# untitled.net
KiCad netlist of a schematic drawn in EAGLE
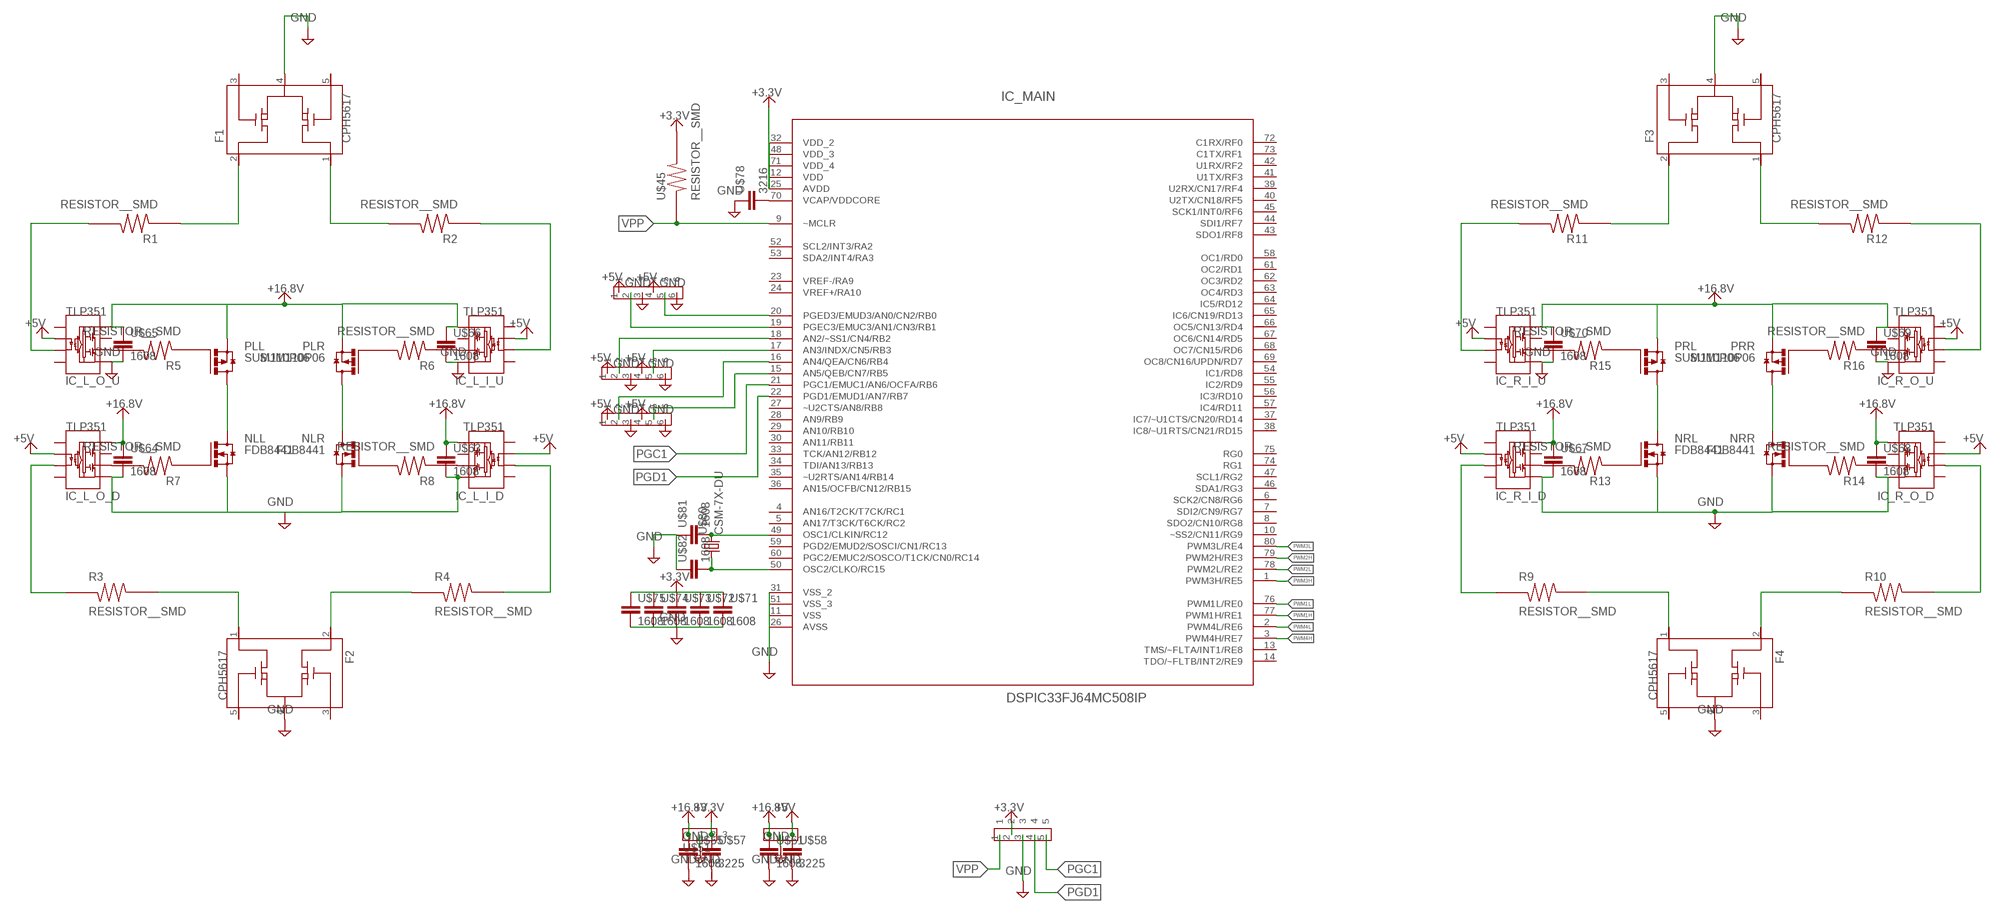
[diagram p0: schematic, sheet 1]

(export (version "E")
  (design (tool "Eeschema 10.0.6"))
  (components
    (comp (ref "F1")
      (value "CPH5617")
      (footprint "eagle-import:CHP-5")
      (libsource (lib "eagle-import") (part "CPH5617"))
    )
    (comp (ref "F2")
      (value "CPH5617")
      (footprint "eagle-import:CHP-5")
      (libsource (lib "eagle-import") (part "CPH5617"))
    )
    (comp (ref "F3")
      (value "CPH5617")
      (footprint "eagle-import:CHP-5")
      (libsource (lib "eagle-import") (part "CPH5617"))
    )
    (comp (ref "F4")
      (value "CPH5617")
      (footprint "eagle-import:CHP-5")
      (libsource (lib "eagle-import") (part "CPH5617"))
    )
    (comp (ref "IC_L_I_D")
      (value "TLP351")
      (footprint "eagle-import:DIL08")
      (libsource (lib "eagle-import") (part "TLP351"))
    )
    (comp (ref "IC_L_I_U")
      (value "TLP351")
      (footprint "eagle-import:DIL08")
      (libsource (lib "eagle-import") (part "TLP351"))
    )
    (comp (ref "IC_L_O_D")
      (value "TLP351")
      (footprint "eagle-import:DIL08")
      (libsource (lib "eagle-import") (part "TLP351"))
    )
    (comp (ref "IC_L_O_U")
      (value "TLP351")
      (footprint "eagle-import:DIL08")
      (libsource (lib "eagle-import") (part "TLP351"))
    )
    (comp (ref "IC_MAIN")
      (value "DSPIC33FJ64MC508IP")
      (footprint "eagle-import:QFP50P1400X1400X120-80N")
      (libsource (lib "eagle-import") (part "DSPIC33FJ64MC508IP"))
    )
    (comp (ref "IC_R_I_D")
      (value "TLP351")
      (footprint "eagle-import:DIL08")
      (libsource (lib "eagle-import") (part "TLP351"))
    )
    (comp (ref "IC_R_I_U")
      (value "TLP351")
      (footprint "eagle-import:DIL08")
      (libsource (lib "eagle-import") (part "TLP351"))
    )
    (comp (ref "IC_R_O_D")
      (value "TLP351")
      (footprint "eagle-import:DIL08")
      (libsource (lib "eagle-import") (part "TLP351"))
    )
    (comp (ref "IC_R_O_U")
      (value "TLP351")
      (footprint "eagle-import:DIL08")
      (libsource (lib "eagle-import") (part "TLP351"))
    )
    (comp (ref "NLL")
      (value "FDB8441")
      (footprint "eagle-import:TO-263")
      (libsource (lib "eagle-import") (part "FDB8441"))
    )
    (comp (ref "NLR")
      (value "FDB8441")
      (footprint "eagle-import:TO-263")
      (libsource (lib "eagle-import") (part "FDB8441"))
    )
    (comp (ref "NRL")
      (value "FDB8441")
      (footprint "eagle-import:TO-263")
      (libsource (lib "eagle-import") (part "FDB8441"))
    )
    (comp (ref "NRR")
      (value "FDB8441")
      (footprint "eagle-import:TO-263")
      (libsource (lib "eagle-import") (part "FDB8441"))
    )
    (comp (ref "PLL")
      (value "SUM110P06")
      (footprint "eagle-import:TO-263")
      (libsource (lib "eagle-import") (part "SUM110P06"))
    )
    (comp (ref "PLR")
      (value "SUM110P06")
      (footprint "eagle-import:TO-263")
      (libsource (lib "eagle-import") (part "SUM110P06"))
    )
    (comp (ref "PRL")
      (value "SUM110P06")
      (footprint "eagle-import:TO-263")
      (libsource (lib "eagle-import") (part "SUM110P06"))
    )
    (comp (ref "PRR")
      (value "SUM110P06")
      (footprint "eagle-import:TO-263")
      (libsource (lib "eagle-import") (part "SUM110P06"))
    )
    (comp (ref "R1")
      (value "RESISTOR__SMD")
      (footprint "eagle-import:1608")
      (libsource (lib "eagle-import") (part "RESISTOR__SMD"))
    )
    (comp (ref "R2")
      (value "RESISTOR__SMD")
      (footprint "eagle-import:1608")
      (libsource (lib "eagle-import") (part "RESISTOR__SMD"))
    )
    (comp (ref "R3")
      (value "RESISTOR__SMD")
      (footprint "eagle-import:1608")
      (libsource (lib "eagle-import") (part "RESISTOR__SMD"))
    )
    (comp (ref "R4")
      (value "RESISTOR__SMD")
      (footprint "eagle-import:1608")
      (libsource (lib "eagle-import") (part "RESISTOR__SMD"))
    )
    (comp (ref "R5")
      (value "RESISTOR__SMD")
      (footprint "eagle-import:1608")
      (libsource (lib "eagle-import") (part "RESISTOR__SMD"))
    )
    (comp (ref "R6")
      (value "RESISTOR__SMD")
      (footprint "eagle-import:1608")
      (libsource (lib "eagle-import") (part "RESISTOR__SMD"))
    )
    (comp (ref "R7")
      (value "RESISTOR__SMD")
      (footprint "eagle-import:1608")
      (libsource (lib "eagle-import") (part "RESISTOR__SMD"))
    )
    (comp (ref "R8")
      (value "RESISTOR__SMD")
      (footprint "eagle-import:1608")
      (libsource (lib "eagle-import") (part "RESISTOR__SMD"))
    )
    (comp (ref "R9")
      (value "RESISTOR__SMD")
      (footprint "eagle-import:1608")
      (libsource (lib "eagle-import") (part "RESISTOR__SMD"))
    )
    (comp (ref "R10")
      (value "RESISTOR__SMD")
      (footprint "eagle-import:1608")
      (libsource (lib "eagle-import") (part "RESISTOR__SMD"))
    )
    (comp (ref "R11")
      (value "RESISTOR__SMD")
      (footprint "eagle-import:1608")
      (libsource (lib "eagle-import") (part "RESISTOR__SMD"))
    )
    (comp (ref "R12")
      (value "RESISTOR__SMD")
      (footprint "eagle-import:1608")
      (libsource (lib "eagle-import") (part "RESISTOR__SMD"))
    )
    (comp (ref "R13")
      (value "RESISTOR__SMD")
      (footprint "eagle-import:1608")
      (libsource (lib "eagle-import") (part "RESISTOR__SMD"))
    )
    (comp (ref "R14")
      (value "RESISTOR__SMD")
      (footprint "eagle-import:1608")
      (libsource (lib "eagle-import") (part "RESISTOR__SMD"))
    )
    (comp (ref "R15")
      (value "RESISTOR__SMD")
      (footprint "eagle-import:1608")
      (libsource (lib "eagle-import") (part "RESISTOR__SMD"))
    )
    (comp (ref "R16")
      (value "RESISTOR__SMD")
      (footprint "eagle-import:1608")
      (libsource (lib "eagle-import") (part "RESISTOR__SMD"))
    )
    (comp (ref "U$1")
      (value "PIN_HEADER_5")
      (footprint "eagle-import:PIN_HEADER_5")
      (libsource (lib "eagle-import") (part "PIN_HEADER_5"))
    )
    (comp (ref "U$4")
      (value "PIN_HEADER_6")
      (footprint "eagle-import:PIN_HEADER_6")
      (libsource (lib "eagle-import") (part "PIN_HEADER_6"))
    )
    (comp (ref "U$5")
      (value "PIN_HEADER_6")
      (footprint "eagle-import:PIN_HEADER_6")
      (libsource (lib "eagle-import") (part "PIN_HEADER_6"))
    )
    (comp (ref "U$20")
      (value "PIN_HEADER_6")
      (footprint "eagle-import:PIN_HEADER_6")
      (libsource (lib "eagle-import") (part "PIN_HEADER_6"))
    )
    (comp (ref "U$45")
      (value "RESISTOR__SMD")
      (footprint "eagle-import:1608")
      (libsource (lib "eagle-import") (part "RESISTOR__SMD"))
    )
    (comp (ref "U$47")
      (value "TA48M05")
      (footprint "eagle-import:ＨＳＩＰ３")
      (libsource (lib "eagle-import") (part "TA48M05"))
    )
    (comp (ref "U$51")
      (value "TA48M033")
      (footprint "eagle-import:ＨＳＩＰ３")
      (libsource (lib "eagle-import") (part "TA48M033"))
    )
    (comp (ref "U$55")
      (value "1608")
      (footprint "eagle-import:1608")
      (libsource (lib "eagle-import") (part "1608"))
    )
    (comp (ref "U$57")
      (value "3225")
      (footprint "eagle-import:3225")
      (libsource (lib "eagle-import") (part "3225"))
    )
    (comp (ref "U$58")
      (value "3225")
      (footprint "eagle-import:3225")
      (libsource (lib "eagle-import") (part "3225"))
    )
    (comp (ref "U$61")
      (value "1608")
      (footprint "eagle-import:1608")
      (libsource (lib "eagle-import") (part "1608"))
    )
    (comp (ref "U$63")
      (value "1608")
      (footprint "eagle-import:1608")
      (libsource (lib "eagle-import") (part "1608"))
    )
    (comp (ref "U$64")
      (value "1608")
      (footprint "eagle-import:1608")
      (libsource (lib "eagle-import") (part "1608"))
    )
    (comp (ref "U$65")
      (value "1608")
      (footprint "eagle-import:1608")
      (libsource (lib "eagle-import") (part "1608"))
    )
    (comp (ref "U$66")
      (value "1608")
      (footprint "eagle-import:1608")
      (libsource (lib "eagle-import") (part "1608"))
    )
    (comp (ref "U$67")
      (value "1608")
      (footprint "eagle-import:1608")
      (libsource (lib "eagle-import") (part "1608"))
    )
    (comp (ref "U$68")
      (value "1608")
      (footprint "eagle-import:1608")
      (libsource (lib "eagle-import") (part "1608"))
    )
    (comp (ref "U$69")
      (value "1608")
      (footprint "eagle-import:1608")
      (libsource (lib "eagle-import") (part "1608"))
    )
    (comp (ref "U$70")
      (value "1608")
      (footprint "eagle-import:1608")
      (libsource (lib "eagle-import") (part "1608"))
    )
    (comp (ref "U$71")
      (value "1608")
      (footprint "eagle-import:1608")
      (libsource (lib "eagle-import") (part "1608"))
    )
    (comp (ref "U$72")
      (value "1608")
      (footprint "eagle-import:1608")
      (libsource (lib "eagle-import") (part "1608"))
    )
    (comp (ref "U$73")
      (value "1608")
      (footprint "eagle-import:1608")
      (libsource (lib "eagle-import") (part "1608"))
    )
    (comp (ref "U$74")
      (value "1608")
      (footprint "eagle-import:1608")
      (libsource (lib "eagle-import") (part "1608"))
    )
    (comp (ref "U$75")
      (value "1608")
      (footprint "eagle-import:1608")
      (libsource (lib "eagle-import") (part "1608"))
    )
    (comp (ref "U$78")
      (value "3216")
      (footprint "eagle-import:3216")
      (libsource (lib "eagle-import") (part "3216"))
    )
    (comp (ref "U$80")
      (value "CSM-7X-DU")
      (footprint "eagle-import:CSM-7X-DU")
      (libsource (lib "eagle-import") (part "CSM-7X-DU"))
    )
    (comp (ref "U$81")
      (value "1608")
      (footprint "eagle-import:1608")
      (libsource (lib "eagle-import") (part "1608"))
    )
    (comp (ref "U$82")
      (value "1608")
      (footprint "eagle-import:1608")
      (libsource (lib "eagle-import") (part "1608"))
    )
  )
  (nets
    (net (code "1") (name "+3.3V") (class "Default")
      (node (ref "IC_MAIN") (pin "12") (pinfunction "VDD_12") (pintype "power_in"))
      (node (ref "IC_MAIN") (pin "25") (pinfunction "AVDD_25") (pintype "power_in"))
      (node (ref "IC_MAIN") (pin "32") (pinfunction "VDD_2_32") (pintype "power_in"))
      (node (ref "IC_MAIN") (pin "48") (pinfunction "VDD_3_48") (pintype "power_in"))
      (node (ref "IC_MAIN") (pin "71") (pinfunction "VDD_4_71") (pintype "power_in"))
      (node (ref "U$1") (pin "2") (pinfunction "2_2") (pintype "bidirectional"))
      (node (ref "U$45") (pin "2") (pinfunction "P$2_2") (pintype "passive"))
      (node (ref "U$51") (pin "3") (pinfunction "3_3") (pintype "bidirectional"))
      (node (ref "U$57") (pin "P$1") (pinfunction "1_P$1") (pintype "passive"))
      (node (ref "U$71") (pin "P$1") (pinfunction "1_P$1") (pintype "passive"))
      (node (ref "U$72") (pin "P$1") (pinfunction "1_P$1") (pintype "passive"))
      (node (ref "U$73") (pin "P$1") (pinfunction "1_P$1") (pintype "passive"))
      (node (ref "U$74") (pin "P$1") (pinfunction "1_P$1") (pintype "passive"))
      (node (ref "U$75") (pin "P$1") (pinfunction "1_P$1") (pintype "passive"))
    )
    (net (code "2") (name "+5V") (class "Default")
      (node (ref "IC_L_I_D") (pin "2") (pinfunction "LED+_2") (pintype "bidirectional"))
      (node (ref "IC_L_I_U") (pin "2") (pinfunction "LED+_2") (pintype "bidirectional"))
      (node (ref "IC_L_O_D") (pin "2") (pinfunction "LED+_2") (pintype "bidirectional"))
      (node (ref "IC_L_O_U") (pin "2") (pinfunction "LED+_2") (pintype "bidirectional"))
      (node (ref "IC_R_I_D") (pin "2") (pinfunction "LED+_2") (pintype "bidirectional"))
      (node (ref "IC_R_I_U") (pin "2") (pinfunction "LED+_2") (pintype "bidirectional"))
      (node (ref "IC_R_O_D") (pin "2") (pinfunction "LED+_2") (pintype "bidirectional"))
      (node (ref "IC_R_O_U") (pin "2") (pinfunction "LED+_2") (pintype "bidirectional"))
      (node (ref "U$20") (pin "1") (pinfunction "1_1") (pintype "bidirectional"))
      (node (ref "U$20") (pin "4") (pinfunction "4_4") (pintype "bidirectional"))
      (node (ref "U$4") (pin "1") (pinfunction "1_1") (pintype "bidirectional"))
      (node (ref "U$4") (pin "4") (pinfunction "4_4") (pintype "bidirectional"))
      (node (ref "U$47") (pin "3") (pinfunction "OUT_3") (pintype "bidirectional"))
      (node (ref "U$5") (pin "1") (pinfunction "1_1") (pintype "bidirectional"))
      (node (ref "U$5") (pin "4") (pinfunction "4_4") (pintype "bidirectional"))
      (node (ref "U$58") (pin "P$1") (pinfunction "1_P$1") (pintype "passive"))
    )
    (net (code "3") (name "+16.8V") (class "Default")
      (node (ref "IC_L_I_D") (pin "8") (pinfunction "VDD_8") (pintype "bidirectional"))
      (node (ref "IC_L_I_U") (pin "8") (pinfunction "VDD_8") (pintype "bidirectional"))
      (node (ref "IC_L_O_D") (pin "8") (pinfunction "VDD_8") (pintype "bidirectional"))
      (node (ref "IC_L_O_U") (pin "8") (pinfunction "VDD_8") (pintype "bidirectional"))
      (node (ref "IC_R_I_D") (pin "8") (pinfunction "VDD_8") (pintype "bidirectional"))
      (node (ref "IC_R_I_U") (pin "8") (pinfunction "VDD_8") (pintype "bidirectional"))
      (node (ref "IC_R_O_D") (pin "8") (pinfunction "VDD_8") (pintype "bidirectional"))
      (node (ref "IC_R_O_U") (pin "8") (pinfunction "VDD_8") (pintype "bidirectional"))
      (node (ref "PLL") (pin "2") (pinfunction "S_2") (pintype "passive"))
      (node (ref "PLR") (pin "2") (pinfunction "S_2") (pintype "passive"))
      (node (ref "PRL") (pin "2") (pinfunction "S_2") (pintype "passive"))
      (node (ref "PRR") (pin "2") (pinfunction "S_2") (pintype "passive"))
      (node (ref "U$47") (pin "1") (pinfunction "IN_1") (pintype "bidirectional"))
      (node (ref "U$51") (pin "1") (pinfunction "1_1") (pintype "bidirectional"))
      (node (ref "U$55") (pin "P$1") (pinfunction "1_P$1") (pintype "passive"))
      (node (ref "U$61") (pin "P$1") (pinfunction "1_P$1") (pintype "passive"))
      (node (ref "U$63") (pin "P$1") (pinfunction "1_P$1") (pintype "passive"))
      (node (ref "U$64") (pin "P$1") (pinfunction "1_P$1") (pintype "passive"))
      (node (ref "U$65") (pin "P$1") (pinfunction "1_P$1") (pintype "passive"))
      (node (ref "U$66") (pin "P$1") (pinfunction "1_P$1") (pintype "passive"))
      (node (ref "U$67") (pin "P$1") (pinfunction "1_P$1") (pintype "passive"))
      (node (ref "U$68") (pin "P$1") (pinfunction "1_P$1") (pintype "passive"))
      (node (ref "U$69") (pin "P$1") (pinfunction "1_P$1") (pintype "passive"))
      (node (ref "U$70") (pin "P$1") (pinfunction "1_P$1") (pintype "passive"))
    )
    (net (code "4") (name "GND") (class "Default")
      (node (ref "F1") (pin "4") (pinfunction "S_4") (pintype "bidirectional"))
      (node (ref "F2") (pin "4") (pinfunction "S_4") (pintype "bidirectional"))
      (node (ref "F3") (pin "4") (pinfunction "S_4") (pintype "bidirectional"))
      (node (ref "F4") (pin "4") (pinfunction "S_4") (pintype "bidirectional"))
      (node (ref "IC_L_I_D") (pin "5") (pinfunction "GND_5") (pintype "bidirectional"))
      (node (ref "IC_L_I_U") (pin "5") (pinfunction "GND_5") (pintype "bidirectional"))
      (node (ref "IC_L_O_D") (pin "5") (pinfunction "GND_5") (pintype "bidirectional"))
      (node (ref "IC_L_O_U") (pin "5") (pinfunction "GND_5") (pintype "bidirectional"))
      (node (ref "IC_MAIN") (pin "11") (pinfunction "VSS_11") (pintype "power_in"))
      (node (ref "IC_MAIN") (pin "26") (pinfunction "AVSS_26") (pintype "power_in"))
      (node (ref "IC_MAIN") (pin "31") (pinfunction "VSS_2_31") (pintype "power_in"))
      (node (ref "IC_MAIN") (pin "51") (pinfunction "VSS_3_51") (pintype "power_in"))
      (node (ref "IC_R_I_D") (pin "5") (pinfunction "GND_5") (pintype "bidirectional"))
      (node (ref "IC_R_I_U") (pin "5") (pinfunction "GND_5") (pintype "bidirectional"))
      (node (ref "IC_R_O_D") (pin "5") (pinfunction "GND_5") (pintype "bidirectional"))
      (node (ref "IC_R_O_U") (pin "5") (pinfunction "GND_5") (pintype "bidirectional"))
      (node (ref "NLL") (pin "2") (pinfunction "S_2") (pintype "passive"))
      (node (ref "NLR") (pin "2") (pinfunction "S_2") (pintype "passive"))
      (node (ref "NRL") (pin "2") (pinfunction "S_2") (pintype "passive"))
      (node (ref "NRR") (pin "2") (pinfunction "S_2") (pintype "passive"))
      (node (ref "U$1") (pin "3") (pinfunction "3_3") (pintype "bidirectional"))
      (node (ref "U$20") (pin "3") (pinfunction "3_3") (pintype "bidirectional"))
      (node (ref "U$20") (pin "6") (pinfunction "6_6") (pintype "bidirectional"))
      (node (ref "U$4") (pin "3") (pinfunction "3_3") (pintype "bidirectional"))
      (node (ref "U$4") (pin "6") (pinfunction "6_6") (pintype "bidirectional"))
      (node (ref "U$47") (pin "2") (pinfunction "GND_2") (pintype "bidirectional"))
      (node (ref "U$5") (pin "3") (pinfunction "3_3") (pintype "bidirectional"))
      (node (ref "U$5") (pin "6") (pinfunction "6_6") (pintype "bidirectional"))
      (node (ref "U$51") (pin "2") (pinfunction "2_2") (pintype "bidirectional"))
      (node (ref "U$55") (pin "P$2") (pinfunction "2_P$2") (pintype "passive"))
      (node (ref "U$57") (pin "P$2") (pinfunction "2_P$2") (pintype "passive"))
      (node (ref "U$58") (pin "P$2") (pinfunction "2_P$2") (pintype "passive"))
      (node (ref "U$61") (pin "P$2") (pinfunction "2_P$2") (pintype "passive"))
      (node (ref "U$63") (pin "P$2") (pinfunction "2_P$2") (pintype "passive"))
      (node (ref "U$64") (pin "P$2") (pinfunction "2_P$2") (pintype "passive"))
      (node (ref "U$65") (pin "P$2") (pinfunction "2_P$2") (pintype "passive"))
      (node (ref "U$66") (pin "P$2") (pinfunction "2_P$2") (pintype "passive"))
      (node (ref "U$67") (pin "P$2") (pinfunction "2_P$2") (pintype "passive"))
      (node (ref "U$68") (pin "P$2") (pinfunction "2_P$2") (pintype "passive"))
      (node (ref "U$69") (pin "P$2") (pinfunction "2_P$2") (pintype "passive"))
      (node (ref "U$70") (pin "P$2") (pinfunction "2_P$2") (pintype "passive"))
      (node (ref "U$71") (pin "P$2") (pinfunction "2_P$2") (pintype "passive"))
      (node (ref "U$72") (pin "P$2") (pinfunction "2_P$2") (pintype "passive"))
      (node (ref "U$73") (pin "P$2") (pinfunction "2_P$2") (pintype "passive"))
      (node (ref "U$74") (pin "P$2") (pinfunction "2_P$2") (pintype "passive"))
      (node (ref "U$75") (pin "P$2") (pinfunction "2_P$2") (pintype "passive"))
      (node (ref "U$78") (pin "P$1") (pinfunction "1_P$1") (pintype "passive"))
      (node (ref "U$81") (pin "P$1") (pinfunction "1_P$1") (pintype "passive"))
      (node (ref "U$82") (pin "P$1") (pinfunction "1_P$1") (pintype "passive"))
    )
    (net (code "5") (name "Net-(F1-D1)") (class "Default")
      (node (ref "F1") (pin "1") (pinfunction "D1_1") (pintype "bidirectional"))
      (node (ref "R2") (pin "2") (pinfunction "P$2_2") (pintype "passive"))
    )
    (net (code "6") (name "Net-(F1-D2)") (class "Default")
      (node (ref "F1") (pin "2") (pinfunction "D2_2") (pintype "bidirectional"))
      (node (ref "R1") (pin "1") (pinfunction "P$1_1") (pintype "passive"))
    )
    (net (code "7") (name "Net-(F2-D1)") (class "Default")
      (node (ref "F2") (pin "1") (pinfunction "D1_1") (pintype "bidirectional"))
      (node (ref "R3") (pin "2") (pinfunction "P$2_2") (pintype "passive"))
    )
    (net (code "8") (name "Net-(F2-D2)") (class "Default")
      (node (ref "F2") (pin "2") (pinfunction "D2_2") (pintype "bidirectional"))
      (node (ref "R4") (pin "1") (pinfunction "P$1_1") (pintype "passive"))
    )
    (net (code "9") (name "Net-(F3-D1)") (class "Default")
      (node (ref "F3") (pin "1") (pinfunction "D1_1") (pintype "bidirectional"))
      (node (ref "R12") (pin "2") (pinfunction "P$2_2") (pintype "passive"))
    )
    (net (code "10") (name "Net-(F3-D2)") (class "Default")
      (node (ref "F3") (pin "2") (pinfunction "D2_2") (pintype "bidirectional"))
      (node (ref "R11") (pin "1") (pinfunction "P$1_1") (pintype "passive"))
    )
    (net (code "11") (name "Net-(F4-D1)") (class "Default")
      (node (ref "F4") (pin "1") (pinfunction "D1_1") (pintype "bidirectional"))
      (node (ref "R9") (pin "2") (pinfunction "P$2_2") (pintype "passive"))
    )
    (net (code "12") (name "Net-(F4-D2)") (class "Default")
      (node (ref "F4") (pin "2") (pinfunction "D2_2") (pintype "bidirectional"))
      (node (ref "R10") (pin "1") (pinfunction "P$1_1") (pintype "passive"))
    )
    (net (code "13") (name "Net-(IC_L_I_D-LED-)") (class "Default")
      (node (ref "IC_L_I_D") (pin "3") (pinfunction "LED-_3") (pintype "bidirectional"))
      (node (ref "R4") (pin "2") (pinfunction "P$2_2") (pintype "passive"))
    )
    (net (code "14") (name "Net-(IC_L_I_D-OUT)") (class "Default")
      (node (ref "IC_L_I_D") (pin "6") (pinfunction "OUT_6") (pintype "output"))
      (node (ref "R8") (pin "1") (pinfunction "P$1_1") (pintype "passive"))
    )
    (net (code "15") (name "Net-(IC_L_I_U-LED-)") (class "Default")
      (node (ref "IC_L_I_U") (pin "3") (pinfunction "LED-_3") (pintype "bidirectional"))
      (node (ref "R2") (pin "1") (pinfunction "P$1_1") (pintype "passive"))
    )
    (net (code "16") (name "Net-(IC_L_I_U-OUT)") (class "Default")
      (node (ref "IC_L_I_U") (pin "6") (pinfunction "OUT_6") (pintype "output"))
      (node (ref "R6") (pin "1") (pinfunction "P$1_1") (pintype "passive"))
    )
    (net (code "17") (name "Net-(IC_L_O_D-LED-)") (class "Default")
      (node (ref "IC_L_O_D") (pin "3") (pinfunction "LED-_3") (pintype "bidirectional"))
      (node (ref "R3") (pin "1") (pinfunction "P$1_1") (pintype "passive"))
    )
    (net (code "18") (name "Net-(IC_L_O_D-OUT)") (class "Default")
      (node (ref "IC_L_O_D") (pin "6") (pinfunction "OUT_6") (pintype "output"))
      (node (ref "R7") (pin "2") (pinfunction "P$2_2") (pintype "passive"))
    )
    (net (code "19") (name "Net-(IC_L_O_U-LED-)") (class "Default")
      (node (ref "IC_L_O_U") (pin "3") (pinfunction "LED-_3") (pintype "bidirectional"))
      (node (ref "R1") (pin "2") (pinfunction "P$2_2") (pintype "passive"))
    )
    (net (code "20") (name "Net-(IC_L_O_U-OUT)") (class "Default")
      (node (ref "IC_L_O_U") (pin "6") (pinfunction "OUT_6") (pintype "output"))
      (node (ref "R5") (pin "2") (pinfunction "P$2_2") (pintype "passive"))
    )
    (net (code "21") (name "Net-(IC_MAIN-AN2{slash}~{SS1{slash}CN4{slash}RB2})") (class "Default")
      (node (ref "IC_MAIN") (pin "18") (pinfunction "AN2/~{SS1/CN4/RB2}_18") (pintype "bidirectional"))
      (node (ref "U$5") (pin "2") (pinfunction "2_2") (pintype "bidirectional"))
    )
    (net (code "22") (name "Net-(IC_MAIN-AN3{slash}INDX{slash}CN5{slash}RB3)") (class "Default")
      (node (ref "IC_MAIN") (pin "17") (pinfunction "AN3/INDX/CN5/RB3_17") (pintype "bidirectional"))
      (node (ref "U$5") (pin "5") (pinfunction "5_5") (pintype "bidirectional"))
    )
    (net (code "23") (name "Net-(IC_MAIN-AN4{slash}QEA{slash}CN6{slash}RB4)") (class "Default")
      (node (ref "IC_MAIN") (pin "16") (pinfunction "AN4/QEA/CN6/RB4_16") (pintype "bidirectional"))
      (node (ref "U$20") (pin "2") (pinfunction "2_2") (pintype "bidirectional"))
    )
    (net (code "24") (name "Net-(IC_MAIN-AN5{slash}QEB{slash}CN7{slash}RB5)") (class "Default")
      (node (ref "IC_MAIN") (pin "15") (pinfunction "AN5/QEB/CN7/RB5_15") (pintype "bidirectional"))
      (node (ref "U$20") (pin "5") (pinfunction "5_5") (pintype "bidirectional"))
    )
    (net (code "25") (name "Net-(IC_MAIN-OSC1{slash}CLKIN{slash}RC12)") (class "Default")
      (node (ref "IC_MAIN") (pin "49") (pinfunction "OSC1/CLKIN/RC12_49") (pintype "bidirectional"))
      (node (ref "U$80") (pin "2") (pinfunction "2_2") (pintype "passive"))
      (node (ref "U$81") (pin "P$2") (pinfunction "2_P$2") (pintype "passive"))
    )
    (net (code "26") (name "Net-(IC_MAIN-OSC2{slash}CLKO{slash}RC15)") (class "Default")
      (node (ref "IC_MAIN") (pin "50") (pinfunction "OSC2/CLKO/RC15_50") (pintype "bidirectional"))
      (node (ref "U$80") (pin "1") (pinfunction "1_1") (pintype "passive"))
      (node (ref "U$82") (pin "P$2") (pinfunction "2_P$2") (pintype "passive"))
    )
    (net (code "27") (name "Net-(IC_MAIN-PGEC3{slash}EMUC3{slash}AN1{slash}CN3{slash}RB1)") (class "Default")
      (node (ref "IC_MAIN") (pin "19") (pinfunction "PGEC3/EMUC3/AN1/CN3/RB1_19") (pintype "bidirectional"))
      (node (ref "U$4") (pin "2") (pinfunction "2_2") (pintype "bidirectional"))
    )
    (net (code "28") (name "Net-(IC_MAIN-PGED3{slash}EMUD3{slash}AN0{slash}CN2{slash}RB0)") (class "Default")
      (node (ref "IC_MAIN") (pin "20") (pinfunction "PGED3/EMUD3/AN0/CN2/RB0_20") (pintype "bidirectional"))
      (node (ref "U$4") (pin "5") (pinfunction "5_5") (pintype "bidirectional"))
    )
    (net (code "29") (name "Net-(IC_MAIN-VCAP{slash}VDDCORE)") (class "Default")
      (node (ref "IC_MAIN") (pin "70") (pinfunction "VCAP/VDDCORE_70") (pintype "power_in"))
      (node (ref "U$78") (pin "P$2") (pinfunction "2_P$2") (pintype "passive"))
    )
    (net (code "30") (name "Net-(IC_R_I_D-LED-)") (class "Default")
      (node (ref "IC_R_I_D") (pin "3") (pinfunction "LED-_3") (pintype "bidirectional"))
      (node (ref "R9") (pin "1") (pinfunction "P$1_1") (pintype "passive"))
    )
    (net (code "31") (name "Net-(IC_R_I_D-OUT)") (class "Default")
      (node (ref "IC_R_I_D") (pin "6") (pinfunction "OUT_6") (pintype "output"))
      (node (ref "R13") (pin "2") (pinfunction "P$2_2") (pintype "passive"))
    )
    (net (code "32") (name "Net-(IC_R_I_U-LED-)") (class "Default")
      (node (ref "IC_R_I_U") (pin "3") (pinfunction "LED-_3") (pintype "bidirectional"))
      (node (ref "R11") (pin "2") (pinfunction "P$2_2") (pintype "passive"))
    )
    (net (code "33") (name "Net-(IC_R_I_U-OUT)") (class "Default")
      (node (ref "IC_R_I_U") (pin "6") (pinfunction "OUT_6") (pintype "output"))
      (node (ref "R15") (pin "2") (pinfunction "P$2_2") (pintype "passive"))
    )
    (net (code "34") (name "Net-(IC_R_O_D-LED-)") (class "Default")
      (node (ref "IC_R_O_D") (pin "3") (pinfunction "LED-_3") (pintype "bidirectional"))
      (node (ref "R10") (pin "2") (pinfunction "P$2_2") (pintype "passive"))
    )
    (net (code "35") (name "Net-(IC_R_O_D-OUT)") (class "Default")
      (node (ref "IC_R_O_D") (pin "6") (pinfunction "OUT_6") (pintype "output"))
      (node (ref "R14") (pin "1") (pinfunction "P$1_1") (pintype "passive"))
    )
    (net (code "36") (name "Net-(IC_R_O_U-LED-)") (class "Default")
      (node (ref "IC_R_O_U") (pin "3") (pinfunction "LED-_3") (pintype "bidirectional"))
      (node (ref "R12") (pin "1") (pinfunction "P$1_1") (pintype "passive"))
    )
    (net (code "37") (name "Net-(IC_R_O_U-OUT)") (class "Default")
      (node (ref "IC_R_O_U") (pin "6") (pinfunction "OUT_6") (pintype "output"))
      (node (ref "R16") (pin "1") (pinfunction "P$1_1") (pintype "passive"))
    )
    (net (code "38") (name "Net-(NLL-D)") (class "Default")
      (node (ref "NLL") (pin "3") (pinfunction "D_3") (pintype "passive"))
      (node (ref "PLL") (pin "3") (pinfunction "D_3") (pintype "passive"))
    )
    (net (code "39") (name "Net-(NLL-G)") (class "Default")
      (node (ref "NLL") (pin "1") (pinfunction "G_1") (pintype "passive"))
      (node (ref "R7") (pin "1") (pinfunction "P$1_1") (pintype "passive"))
    )
    (net (code "40") (name "Net-(NLR-D)") (class "Default")
      (node (ref "NLR") (pin "3") (pinfunction "D_3") (pintype "passive"))
      (node (ref "PLR") (pin "3") (pinfunction "D_3") (pintype "passive"))
    )
    (net (code "41") (name "Net-(NLR-G)") (class "Default")
      (node (ref "NLR") (pin "1") (pinfunction "G_1") (pintype "passive"))
      (node (ref "R8") (pin "2") (pinfunction "P$2_2") (pintype "passive"))
    )
    (net (code "42") (name "Net-(NRL-D)") (class "Default")
      (node (ref "NRL") (pin "3") (pinfunction "D_3") (pintype "passive"))
      (node (ref "PRL") (pin "3") (pinfunction "D_3") (pintype "passive"))
    )
    (net (code "43") (name "Net-(NRL-G)") (class "Default")
      (node (ref "NRL") (pin "1") (pinfunction "G_1") (pintype "passive"))
      (node (ref "R13") (pin "1") (pinfunction "P$1_1") (pintype "passive"))
    )
    (net (code "44") (name "Net-(NRR-D)") (class "Default")
      (node (ref "NRR") (pin "3") (pinfunction "D_3") (pintype "passive"))
      (node (ref "PRR") (pin "3") (pinfunction "D_3") (pintype "passive"))
    )
    (net (code "45") (name "Net-(NRR-G)") (class "Default")
      (node (ref "NRR") (pin "1") (pinfunction "G_1") (pintype "passive"))
      (node (ref "R14") (pin "2") (pinfunction "P$2_2") (pintype "passive"))
    )
    (net (code "46") (name "Net-(PLL-G)") (class "Default")
      (node (ref "PLL") (pin "1") (pinfunction "G_1") (pintype "passive"))
      (node (ref "R5") (pin "1") (pinfunction "P$1_1") (pintype "passive"))
    )
    (net (code "47") (name "Net-(PLR-G)") (class "Default")
      (node (ref "PLR") (pin "1") (pinfunction "G_1") (pintype "passive"))
      (node (ref "R6") (pin "2") (pinfunction "P$2_2") (pintype "passive"))
    )
    (net (code "48") (name "Net-(PRL-G)") (class "Default")
      (node (ref "PRL") (pin "1") (pinfunction "G_1") (pintype "passive"))
      (node (ref "R15") (pin "1") (pinfunction "P$1_1") (pintype "passive"))
    )
    (net (code "49") (name "Net-(PRR-G)") (class "Default")
      (node (ref "PRR") (pin "1") (pinfunction "G_1") (pintype "passive"))
      (node (ref "R16") (pin "2") (pinfunction "P$2_2") (pintype "passive"))
    )
    (net (code "50") (name "PGC1") (class "Default")
      (node (ref "IC_MAIN") (pin "21") (pinfunction "PGC1/EMUC1/AN6/OCFA/RB6_21") (pintype "bidirectional"))
      (node (ref "U$1") (pin "5") (pinfunction "5_5") (pintype "bidirectional"))
    )
    (net (code "51") (name "PGD1") (class "Default")
      (node (ref "IC_MAIN") (pin "22") (pinfunction "PGD1/EMUD1/AN7/RB7_22") (pintype "bidirectional"))
      (node (ref "U$1") (pin "4") (pinfunction "4_4") (pintype "bidirectional"))
    )
    (net (code "52") (name "PWM1H") (class "Default")
      (node (ref "IC_MAIN") (pin "77") (pinfunction "PWM1H/RE1_77") (pintype "bidirectional"))
    )
    (net (code "53") (name "PWM1L") (class "Default")
      (node (ref "IC_MAIN") (pin "76") (pinfunction "PWM1L/RE0_76") (pintype "bidirectional"))
    )
    (net (code "54") (name "PWM2H") (class "Default")
      (node (ref "IC_MAIN") (pin "79") (pinfunction "PWM2H/RE3_79") (pintype "bidirectional"))
    )
    (net (code "55") (name "PWM2L") (class "Default")
      (node (ref "IC_MAIN") (pin "78") (pinfunction "PWM2L/RE2_78") (pintype "bidirectional"))
    )
    (net (code "56") (name "PWM3H") (class "Default")
      (node (ref "IC_MAIN") (pin "1") (pinfunction "PWM3H/RE5_1") (pintype "bidirectional"))
    )
    (net (code "57") (name "PWM3L") (class "Default")
      (node (ref "IC_MAIN") (pin "80") (pinfunction "PWM3L/RE4_80") (pintype "bidirectional"))
    )
    (net (code "58") (name "PWM4H") (class "Default")
      (node (ref "IC_MAIN") (pin "3") (pinfunction "PWM4H/RE7_3") (pintype "bidirectional"))
    )
    (net (code "59") (name "PWM4L") (class "Default")
      (node (ref "IC_MAIN") (pin "2") (pinfunction "PWM4L/RE6_2") (pintype "bidirectional"))
    )
    (net (code "60") (name "VPP") (class "Default")
      (node (ref "IC_MAIN") (pin "9") (pinfunction "~{MCLR}_9") (pintype "input"))
      (node (ref "U$1") (pin "1") (pinfunction "1_1") (pintype "bidirectional"))
      (node (ref "U$45") (pin "1") (pinfunction "P$1_1") (pintype "passive"))
    )
    (net (code "61") (name "unconnected-(F1-G1-Pad5)") (class "Default")
      (node (ref "F1") (pin "5") (pinfunction "G1_5") (pintype "bidirectional"))
    )
    (net (code "62") (name "unconnected-(F1-G2-Pad3)") (class "Default")
      (node (ref "F1") (pin "3") (pinfunction "G2_3") (pintype "bidirectional"))
    )
    (net (code "63") (name "unconnected-(F2-G1-Pad5)") (class "Default")
      (node (ref "F2") (pin "5") (pinfunction "G1_5") (pintype "bidirectional"))
    )
    (net (code "64") (name "unconnected-(F2-G2-Pad3)") (class "Default")
      (node (ref "F2") (pin "3") (pinfunction "G2_3") (pintype "bidirectional"))
    )
    (net (code "65") (name "unconnected-(F3-G1-Pad5)") (class "Default")
      (node (ref "F3") (pin "5") (pinfunction "G1_5") (pintype "bidirectional"))
    )
    (net (code "66") (name "unconnected-(F3-G2-Pad3)") (class "Default")
      (node (ref "F3") (pin "3") (pinfunction "G2_3") (pintype "bidirectional"))
    )
    (net (code "67") (name "unconnected-(F4-G1-Pad5)") (class "Default")
      (node (ref "F4") (pin "5") (pinfunction "G1_5") (pintype "bidirectional"))
    )
    (net (code "68") (name "unconnected-(F4-G2-Pad3)") (class "Default")
      (node (ref "F4") (pin "3") (pinfunction "G2_3") (pintype "bidirectional"))
    )
    (net (code "69") (name "unconnected-(IC_L_I_D-NC1-Pad1)") (class "Default")
      (node (ref "IC_L_I_D") (pin "1") (pinfunction "NC1_1") (pintype "no_connect"))
    )
    (net (code "70") (name "unconnected-(IC_L_I_D-NC4-Pad4)") (class "Default")
      (node (ref "IC_L_I_D") (pin "4") (pinfunction "NC4_4") (pintype "no_connect"))
    )
    (net (code "71") (name "unconnected-(IC_L_I_D-NC7-Pad7)") (class "Default")
      (node (ref "IC_L_I_D") (pin "7") (pinfunction "NC7_7") (pintype "no_connect"))
    )
    (net (code "72") (name "unconnected-(IC_L_I_U-NC1-Pad1)") (class "Default")
      (node (ref "IC_L_I_U") (pin "1") (pinfunction "NC1_1") (pintype "no_connect"))
    )
    (net (code "73") (name "unconnected-(IC_L_I_U-NC4-Pad4)") (class "Default")
      (node (ref "IC_L_I_U") (pin "4") (pinfunction "NC4_4") (pintype "no_connect"))
    )
    (net (code "74") (name "unconnected-(IC_L_I_U-NC7-Pad7)") (class "Default")
      (node (ref "IC_L_I_U") (pin "7") (pinfunction "NC7_7") (pintype "no_connect"))
    )
    (net (code "75") (name "unconnected-(IC_L_O_D-NC1-Pad1)") (class "Default")
      (node (ref "IC_L_O_D") (pin "1") (pinfunction "NC1_1") (pintype "no_connect"))
    )
    (net (code "76") (name "unconnected-(IC_L_O_D-NC4-Pad4)") (class "Default")
      (node (ref "IC_L_O_D") (pin "4") (pinfunction "NC4_4") (pintype "no_connect"))
    )
    (net (code "77") (name "unconnected-(IC_L_O_D-NC7-Pad7)") (class "Default")
      (node (ref "IC_L_O_D") (pin "7") (pinfunction "NC7_7") (pintype "no_connect"))
    )
    (net (code "78") (name "unconnected-(IC_L_O_U-NC1-Pad1)") (class "Default")
      (node (ref "IC_L_O_U") (pin "1") (pinfunction "NC1_1") (pintype "no_connect"))
    )
    (net (code "79") (name "unconnected-(IC_L_O_U-NC4-Pad4)") (class "Default")
      (node (ref "IC_L_O_U") (pin "4") (pinfunction "NC4_4") (pintype "no_connect"))
    )
    (net (code "80") (name "unconnected-(IC_L_O_U-NC7-Pad7)") (class "Default")
      (node (ref "IC_L_O_U") (pin "7") (pinfunction "NC7_7") (pintype "no_connect"))
    )
    (net (code "81") (name "unconnected-(IC_MAIN-AN9{slash}RB9-Pad28)") (class "Default")
      (node (ref "IC_MAIN") (pin "28") (pinfunction "AN9/RB9_28") (pintype "bidirectional"))
    )
    (net (code "82") (name "unconnected-(IC_MAIN-AN10{slash}RB10-Pad29)") (class "Default")
      (node (ref "IC_MAIN") (pin "29") (pinfunction "AN10/RB10_29") (pintype "bidirectional"))
    )
    (net (code "83") (name "unconnected-(IC_MAIN-AN11{slash}RB11-Pad30)") (class "Default")
      (node (ref "IC_MAIN") (pin "30") (pinfunction "AN11/RB11_30") (pintype "bidirectional"))
    )
    (net (code "84") (name "unconnected-(IC_MAIN-AN15{slash}OCFB{slash}CN12{slash}RB15-Pad36)") (class "Default")
      (node (ref "IC_MAIN") (pin "36") (pinfunction "AN15/OCFB/CN12/RB15_36") (pintype "bidirectional"))
    )
    (net (code "85") (name "unconnected-(IC_MAIN-AN16{slash}T2CK{slash}T7CK{slash}RC1-Pad4)") (class "Default")
      (node (ref "IC_MAIN") (pin "4") (pinfunction "AN16/T2CK/T7CK/RC1_4") (pintype "bidirectional"))
    )
    (net (code "86") (name "unconnected-(IC_MAIN-AN17{slash}T3CK{slash}T6CK{slash}RC2-Pad5)") (class "Default")
      (node (ref "IC_MAIN") (pin "5") (pinfunction "AN17/T3CK/T6CK/RC2_5") (pintype "bidirectional"))
    )
    (net (code "87") (name "unconnected-(IC_MAIN-C1RX{slash}RF0-Pad72)") (class "Default")
      (node (ref "IC_MAIN") (pin "72") (pinfunction "C1RX/RF0_72") (pintype "bidirectional"))
    )
    (net (code "88") (name "unconnected-(IC_MAIN-C1TX{slash}RF1-Pad73)") (class "Default")
      (node (ref "IC_MAIN") (pin "73") (pinfunction "C1TX/RF1_73") (pintype "bidirectional"))
    )
    (net (code "89") (name "unconnected-(IC_MAIN-IC1{slash}RD8-Pad54)") (class "Default")
      (node (ref "IC_MAIN") (pin "54") (pinfunction "IC1/RD8_54") (pintype "bidirectional"))
    )
    (net (code "90") (name "unconnected-(IC_MAIN-IC2{slash}RD9-Pad55)") (class "Default")
      (node (ref "IC_MAIN") (pin "55") (pinfunction "IC2/RD9_55") (pintype "bidirectional"))
    )
    (net (code "91") (name "unconnected-(IC_MAIN-IC3{slash}RD10-Pad56)") (class "Default")
      (node (ref "IC_MAIN") (pin "56") (pinfunction "IC3/RD10_56") (pintype "bidirectional"))
    )
    (net (code "92") (name "unconnected-(IC_MAIN-IC4{slash}RD11-Pad57)") (class "Default")
      (node (ref "IC_MAIN") (pin "57") (pinfunction "IC4/RD11_57") (pintype "bidirectional"))
    )
    (net (code "93") (name "unconnected-(IC_MAIN-IC5{slash}RD12-Pad64)") (class "Default")
      (node (ref "IC_MAIN") (pin "64") (pinfunction "IC5/RD12_64") (pintype "bidirectional"))
    )
    (net (code "94") (name "unconnected-(IC_MAIN-IC6{slash}CN19{slash}RD13-Pad65)") (class "Default")
      (node (ref "IC_MAIN") (pin "65") (pinfunction "IC6/CN19/RD13_65") (pintype "bidirectional"))
    )
    (net (code "95") (name "unconnected-(IC_MAIN-IC7{slash}~{U1CTS{slash}CN20{slash}RD14}-Pad37)") (class "Default")
      (node (ref "IC_MAIN") (pin "37") (pinfunction "IC7/~{U1CTS/CN20/RD14}_37") (pintype "bidirectional"))
    )
    (net (code "96") (name "unconnected-(IC_MAIN-IC8{slash}~{U1RTS{slash}CN21{slash}RD15}-Pad38)") (class "Default")
      (node (ref "IC_MAIN") (pin "38") (pinfunction "IC8/~{U1RTS/CN21/RD15}_38") (pintype "bidirectional"))
    )
    (net (code "97") (name "unconnected-(IC_MAIN-OC1{slash}RD0-Pad58)") (class "Default")
      (node (ref "IC_MAIN") (pin "58") (pinfunction "OC1/RD0_58") (pintype "bidirectional"))
    )
    (net (code "98") (name "unconnected-(IC_MAIN-OC2{slash}RD1-Pad61)") (class "Default")
      (node (ref "IC_MAIN") (pin "61") (pinfunction "OC2/RD1_61") (pintype "bidirectional"))
    )
    (net (code "99") (name "unconnected-(IC_MAIN-OC3{slash}RD2-Pad62)") (class "Default")
      (node (ref "IC_MAIN") (pin "62") (pinfunction "OC3/RD2_62") (pintype "bidirectional"))
    )
    (net (code "100") (name "unconnected-(IC_MAIN-OC4{slash}RD3-Pad63)") (class "Default")
      (node (ref "IC_MAIN") (pin "63") (pinfunction "OC4/RD3_63") (pintype "bidirectional"))
    )
    (net (code "101") (name "unconnected-(IC_MAIN-OC5{slash}CN13{slash}RD4-Pad66)") (class "Default")
      (node (ref "IC_MAIN") (pin "66") (pinfunction "OC5/CN13/RD4_66") (pintype "bidirectional"))
    )
    (net (code "102") (name "unconnected-(IC_MAIN-OC6{slash}CN14{slash}RD5-Pad67)") (class "Default")
      (node (ref "IC_MAIN") (pin "67") (pinfunction "OC6/CN14/RD5_67") (pintype "bidirectional"))
    )
    (net (code "103") (name "unconnected-(IC_MAIN-OC7{slash}CN15{slash}RD6-Pad68)") (class "Default")
      (node (ref "IC_MAIN") (pin "68") (pinfunction "OC7/CN15/RD6_68") (pintype "bidirectional"))
    )
    (net (code "104") (name "unconnected-(IC_MAIN-OC8{slash}CN16{slash}UPDN{slash}RD7-Pad69)") (class "Default")
      (node (ref "IC_MAIN") (pin "69") (pinfunction "OC8/CN16/UPDN/RD7_69") (pintype "bidirectional"))
    )
    (net (code "105") (name "unconnected-(IC_MAIN-PGC2{slash}EMUC2{slash}SOSCO{slash}T1CK{slash}CN0{slash}RC14-Pad60)") (class "Default")
      (node (ref "IC_MAIN") (pin "60") (pinfunction "PGC2/EMUC2/SOSCO/T1CK/CN0/RC14_60") (pintype "bidirectional"))
    )
    (net (code "106") (name "unconnected-(IC_MAIN-PGD2{slash}EMUD2{slash}SOSCI{slash}CN1{slash}RC13-Pad59)") (class "Default")
      (node (ref "IC_MAIN") (pin "59") (pinfunction "PGD2/EMUD2/SOSCI/CN1/RC13_59") (pintype "bidirectional"))
    )
    (net (code "107") (name "unconnected-(IC_MAIN-RG0-Pad75)") (class "Default")
      (node (ref "IC_MAIN") (pin "75") (pinfunction "RG0_75") (pintype "bidirectional"))
    )
    (net (code "108") (name "unconnected-(IC_MAIN-RG1-Pad74)") (class "Default")
      (node (ref "IC_MAIN") (pin "74") (pinfunction "RG1_74") (pintype "bidirectional"))
    )
    (net (code "109") (name "unconnected-(IC_MAIN-SCK1{slash}INT0{slash}RF6-Pad45)") (class "Default")
      (node (ref "IC_MAIN") (pin "45") (pinfunction "SCK1/INT0/RF6_45") (pintype "bidirectional"))
    )
    (net (code "110") (name "unconnected-(IC_MAIN-SCK2{slash}CN8{slash}RG6-Pad6)") (class "Default")
      (node (ref "IC_MAIN") (pin "6") (pinfunction "SCK2/CN8/RG6_6") (pintype "bidirectional"))
    )
    (net (code "111") (name "unconnected-(IC_MAIN-SCL1{slash}RG2-Pad47)") (class "Default")
      (node (ref "IC_MAIN") (pin "47") (pinfunction "SCL1/RG2_47") (pintype "bidirectional"))
    )
    (net (code "112") (name "unconnected-(IC_MAIN-SCL2{slash}INT3{slash}RA2-Pad52)") (class "Default")
      (node (ref "IC_MAIN") (pin "52") (pinfunction "SCL2/INT3/RA2_52") (pintype "bidirectional"))
    )
    (net (code "113") (name "unconnected-(IC_MAIN-SDA1{slash}RG3-Pad46)") (class "Default")
      (node (ref "IC_MAIN") (pin "46") (pinfunction "SDA1/RG3_46") (pintype "bidirectional"))
    )
    (net (code "114") (name "unconnected-(IC_MAIN-SDA2{slash}INT4{slash}RA3-Pad53)") (class "Default")
      (node (ref "IC_MAIN") (pin "53") (pinfunction "SDA2/INT4/RA3_53") (pintype "bidirectional"))
    )
    (net (code "115") (name "unconnected-(IC_MAIN-SDI1{slash}RF7-Pad44)") (class "Default")
      (node (ref "IC_MAIN") (pin "44") (pinfunction "SDI1/RF7_44") (pintype "bidirectional"))
    )
    (net (code "116") (name "unconnected-(IC_MAIN-SDI2{slash}CN9{slash}RG7-Pad7)") (class "Default")
      (node (ref "IC_MAIN") (pin "7") (pinfunction "SDI2/CN9/RG7_7") (pintype "bidirectional"))
    )
    (net (code "117") (name "unconnected-(IC_MAIN-SDO1{slash}RF8-Pad43)") (class "Default")
      (node (ref "IC_MAIN") (pin "43") (pinfunction "SDO1/RF8_43") (pintype "bidirectional"))
    )
    (net (code "118") (name "unconnected-(IC_MAIN-SDO2{slash}CN10{slash}RG8-Pad8)") (class "Default")
      (node (ref "IC_MAIN") (pin "8") (pinfunction "SDO2/CN10/RG8_8") (pintype "bidirectional"))
    )
    (net (code "119") (name "unconnected-(IC_MAIN-TCK{slash}AN12{slash}RB12-Pad33)") (class "Default")
      (node (ref "IC_MAIN") (pin "33") (pinfunction "TCK/AN12/RB12_33") (pintype "bidirectional"))
    )
    (net (code "120") (name "unconnected-(IC_MAIN-TDI{slash}AN13{slash}RB13-Pad34)") (class "Default")
      (node (ref "IC_MAIN") (pin "34") (pinfunction "TDI/AN13/RB13_34") (pintype "bidirectional"))
    )
    (net (code "121") (name "unconnected-(IC_MAIN-TDO{slash}~{FLTB{slash}INT2{slash}RE9}-Pad14)") (class "Default")
      (node (ref "IC_MAIN") (pin "14") (pinfunction "TDO/~{FLTB/INT2/RE9}_14") (pintype "bidirectional"))
    )
    (net (code "122") (name "unconnected-(IC_MAIN-TMS{slash}~{FLTA{slash}INT1{slash}RE8}-Pad13)") (class "Default")
      (node (ref "IC_MAIN") (pin "13") (pinfunction "TMS/~{FLTA/INT1/RE8}_13") (pintype "bidirectional"))
    )
    (net (code "123") (name "unconnected-(IC_MAIN-U1RX{slash}RF2-Pad42)") (class "Default")
      (node (ref "IC_MAIN") (pin "42") (pinfunction "U1RX/RF2_42") (pintype "bidirectional"))
    )
    (net (code "124") (name "unconnected-(IC_MAIN-U1TX{slash}RF3-Pad41)") (class "Default")
      (node (ref "IC_MAIN") (pin "41") (pinfunction "U1TX/RF3_41") (pintype "bidirectional"))
    )
    (net (code "125") (name "unconnected-(IC_MAIN-U2RX{slash}CN17{slash}RF4-Pad39)") (class "Default")
      (node (ref "IC_MAIN") (pin "39") (pinfunction "U2RX/CN17/RF4_39") (pintype "bidirectional"))
    )
    (net (code "126") (name "unconnected-(IC_MAIN-U2TX{slash}CN18{slash}RF5-Pad40)") (class "Default")
      (node (ref "IC_MAIN") (pin "40") (pinfunction "U2TX/CN18/RF5_40") (pintype "bidirectional"))
    )
    (net (code "127") (name "unconnected-(IC_MAIN-VREF+{slash}RA10-Pad24)") (class "Default")
      (node (ref "IC_MAIN") (pin "24") (pinfunction "VREF+/RA10_24") (pintype "bidirectional"))
    )
    (net (code "128") (name "unconnected-(IC_MAIN-VREF-{slash}RA9-Pad23)") (class "Default")
      (node (ref "IC_MAIN") (pin "23") (pinfunction "VREF-/RA9_23") (pintype "bidirectional"))
    )
    (net (code "129") (name "unconnected-(IC_MAIN-~{SS2{slash}CN11{slash}RG9}-Pad10)") (class "Default")
      (node (ref "IC_MAIN") (pin "10") (pinfunction "~{SS2/CN11/RG9}_10") (pintype "bidirectional"))
    )
    (net (code "130") (name "unconnected-(IC_MAIN-~{U2CTS{slash}AN8{slash}RB8}-Pad27)") (class "Default")
      (node (ref "IC_MAIN") (pin "27") (pinfunction "~{U2CTS/AN8/RB8}_27") (pintype "bidirectional"))
    )
    (net (code "131") (name "unconnected-(IC_MAIN-~{U2RTS{slash}AN14{slash}RB14}-Pad35)") (class "Default")
      (node (ref "IC_MAIN") (pin "35") (pinfunction "~{U2RTS/AN14/RB14}_35") (pintype "bidirectional"))
    )
    (net (code "132") (name "unconnected-(IC_R_I_D-NC1-Pad1)") (class "Default")
      (node (ref "IC_R_I_D") (pin "1") (pinfunction "NC1_1") (pintype "no_connect"))
    )
    (net (code "133") (name "unconnected-(IC_R_I_D-NC4-Pad4)") (class "Default")
      (node (ref "IC_R_I_D") (pin "4") (pinfunction "NC4_4") (pintype "no_connect"))
    )
    (net (code "134") (name "unconnected-(IC_R_I_D-NC7-Pad7)") (class "Default")
      (node (ref "IC_R_I_D") (pin "7") (pinfunction "NC7_7") (pintype "no_connect"))
    )
    (net (code "135") (name "unconnected-(IC_R_I_U-NC1-Pad1)") (class "Default")
      (node (ref "IC_R_I_U") (pin "1") (pinfunction "NC1_1") (pintype "no_connect"))
    )
    (net (code "136") (name "unconnected-(IC_R_I_U-NC4-Pad4)") (class "Default")
      (node (ref "IC_R_I_U") (pin "4") (pinfunction "NC4_4") (pintype "no_connect"))
    )
    (net (code "137") (name "unconnected-(IC_R_I_U-NC7-Pad7)") (class "Default")
      (node (ref "IC_R_I_U") (pin "7") (pinfunction "NC7_7") (pintype "no_connect"))
    )
    (net (code "138") (name "unconnected-(IC_R_O_D-NC1-Pad1)") (class "Default")
      (node (ref "IC_R_O_D") (pin "1") (pinfunction "NC1_1") (pintype "no_connect"))
    )
    (net (code "139") (name "unconnected-(IC_R_O_D-NC4-Pad4)") (class "Default")
      (node (ref "IC_R_O_D") (pin "4") (pinfunction "NC4_4") (pintype "no_connect"))
    )
    (net (code "140") (name "unconnected-(IC_R_O_D-NC7-Pad7)") (class "Default")
      (node (ref "IC_R_O_D") (pin "7") (pinfunction "NC7_7") (pintype "no_connect"))
    )
    (net (code "141") (name "unconnected-(IC_R_O_U-NC1-Pad1)") (class "Default")
      (node (ref "IC_R_O_U") (pin "1") (pinfunction "NC1_1") (pintype "no_connect"))
    )
    (net (code "142") (name "unconnected-(IC_R_O_U-NC4-Pad4)") (class "Default")
      (node (ref "IC_R_O_U") (pin "4") (pinfunction "NC4_4") (pintype "no_connect"))
    )
    (net (code "143") (name "unconnected-(IC_R_O_U-NC7-Pad7)") (class "Default")
      (node (ref "IC_R_O_U") (pin "7") (pinfunction "NC7_7") (pintype "no_connect"))
    )
  )
)
